# design.net
KiCad netlist of a schematic drawn in Altium Designer
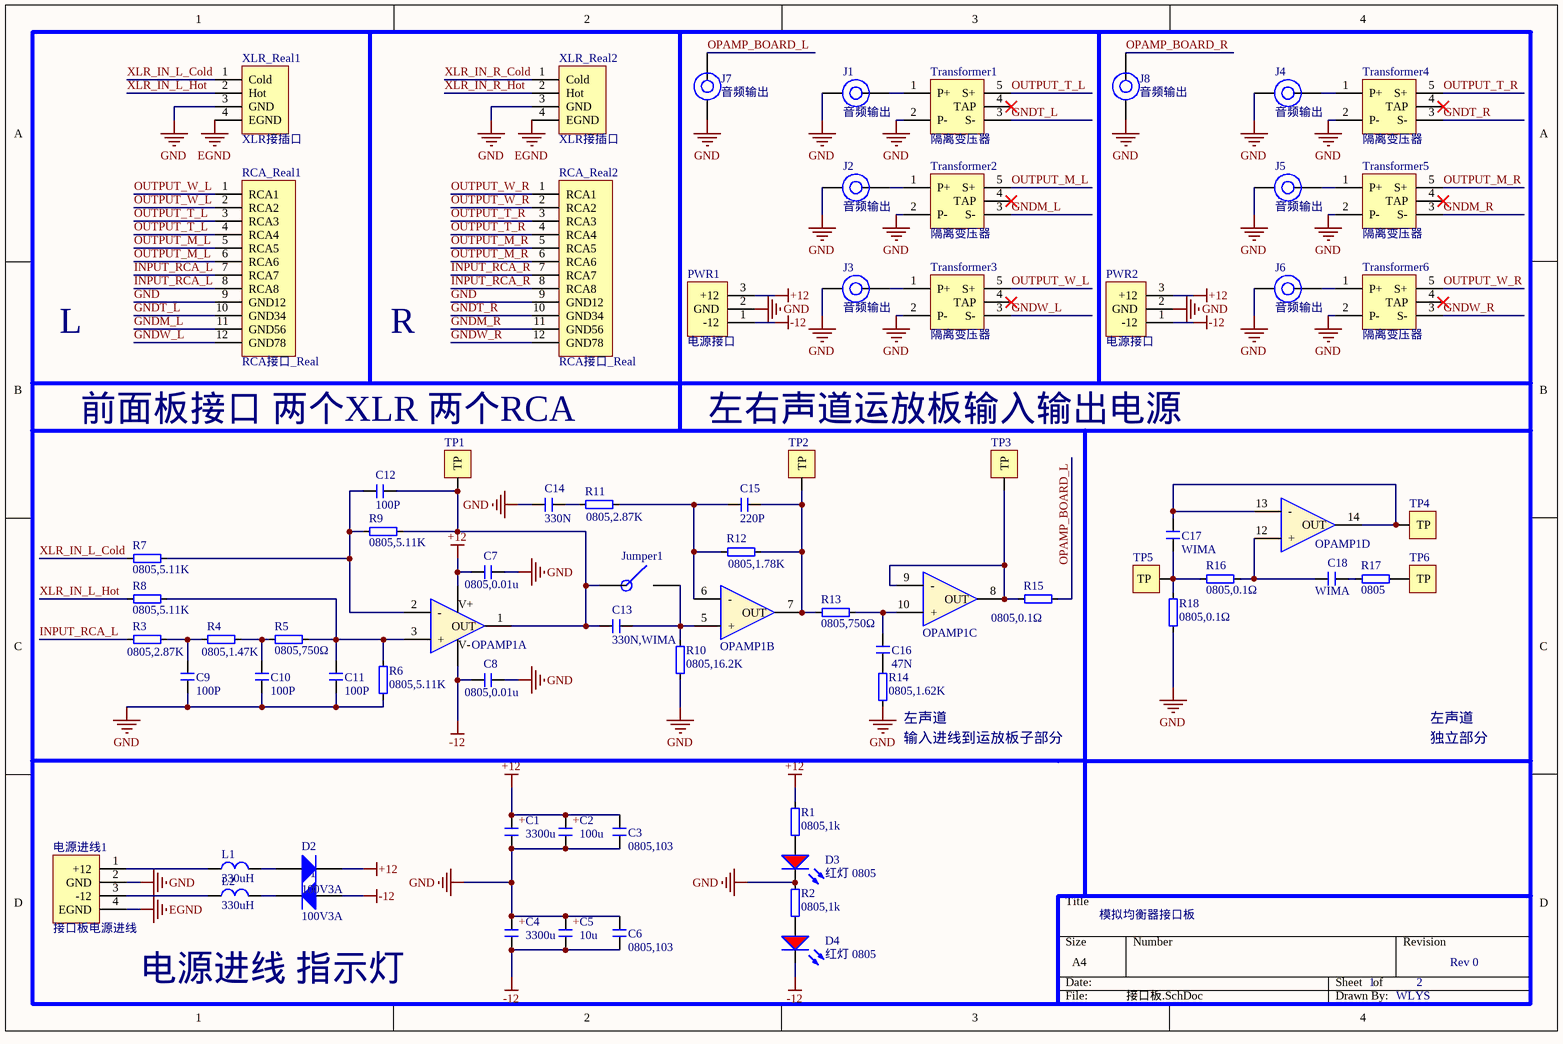
[diagram p0: 接口板.SchDoc]

(export (version "E")
  (design (tool "Eeschema 10.0.6"))
  (components
    (comp (ref "C1")
      (value "3300u")
      (footprint "CAP 7.5*16*31.5 - BK")
      (libsource (lib "模拟均衡器") (part "C直插电解"))
    )
    (comp (ref "C2") (value "100u") (footprint "CAP 2.5*6.3*11.2") (libsource (lib "模拟均衡器") (part "C直插电解")))
    (comp (ref "C3") (value "0805,103") (footprint "0805_C") (libsource (lib "模拟均衡器") (part "C0805")))
    (comp (ref "C4")
      (value "3300u")
      (footprint "CAP 7.5*16*31.5 - BK")
      (libsource (lib "模拟均衡器") (part "C直插电解"))
    )
    (comp (ref "C5") (value "10u") (footprint "CAP 2.5*6.3*11.2") (libsource (lib "模拟均衡器") (part "C直插电解")))
    (comp (ref "C6") (value "0805,103") (footprint "0805_C") (libsource (lib "模拟均衡器") (part "C0805")))
    (comp (ref "C7") (value "0805,0.01u") (footprint "0805_C") (libsource (lib "模拟均衡器") (part "C0805")))
    (comp (ref "C8") (value "0805,0.01u") (footprint "0805_C") (libsource (lib "模拟均衡器") (part "C0805")))
    (comp (ref "C9") (value "100P") (footprint "WIMA_5mm") (libsource (lib "模拟均衡器") (part "WIMA_CAP_100P")))
    (comp (ref "C10") (value "100P") (footprint "WIMA_5mm") (libsource (lib "模拟均衡器") (part "WIMA_CAP_100P")))
    (comp (ref "C11") (value "100P") (footprint "WIMA_5mm") (libsource (lib "模拟均衡器") (part "WIMA_CAP_100P")))
    (comp (ref "C12") (value "100P") (footprint "WIMA_5mm") (libsource (lib "模拟均衡器") (part "WIMA_CAP_100P")))
    (comp (ref "C13")
      (value "330N,WIMA")
      (footprint "WIMA_5mmPin*10mmL")
      (libsource (lib "模拟均衡器") (part "WIMA_CAP_330N"))
    )
    (comp (ref "C14")
      (value "330N")
      (footprint "WIMA_5mmPin*10mmL")
      (libsource (lib "模拟均衡器") (part "WIMA_CAP_330N"))
    )
    (comp (ref "C15") (value "220P") (footprint "WIMA_5mm") (libsource (lib "模拟均衡器") (part "WIMA_CAP_220P")))
    (comp (ref "C16") (value "47N") (footprint "WIMA_5mm") (libsource (lib "模拟均衡器") (part "WIMA_CAP_47N")))
    (comp (ref "C17") (value "WIMA") (footprint "WIMA_5mm") (libsource (lib "模拟均衡器") (part "WIMA_CAP_100P")))
    (comp (ref "C18") (value "WIMA") (footprint "WIMA_5mm") (libsource (lib "模拟均衡器") (part "WIMA_CAP_100P")))
    (comp (ref "D1") (value "100V3A") (footprint "DO-201AD") (libsource (lib "模拟均衡器") (part "1N5401")))
    (comp (ref "D2") (value "100V3A") (footprint "DO-201AD") (libsource (lib "模拟均衡器") (part "1N5401")))
    (comp (ref "D3")
      (value "红灯 0805")
      (footprint "0805_LED_S3")
      (description "发光二极管")
      (libsource (lib "模拟均衡器") (part "0805 红灯"))
    )
    (comp (ref "D4")
      (value "红灯 0805")
      (footprint "0805_LED_S3")
      (description "发光二极管")
      (libsource (lib "模拟均衡器") (part "0805 红灯"))
    )
    (comp (ref "J1") (value "音频输出") (footprint "XH2.54-LI-2P") (libsource (lib "模拟均衡器") (part "音频输出")))
    (comp (ref "J2") (value "音频输出") (footprint "XH2.54-LI-2P") (libsource (lib "模拟均衡器") (part "音频输出")))
    (comp (ref "J3") (value "音频输出") (footprint "XH2.54-LI-2P") (libsource (lib "模拟均衡器") (part "音频输出")))
    (comp (ref "J4") (value "音频输出") (footprint "XH2.54-LI-2P") (libsource (lib "模拟均衡器") (part "音频输出")))
    (comp (ref "J5") (value "音频输出") (footprint "XH2.54-LI-2P") (libsource (lib "模拟均衡器") (part "音频输出")))
    (comp (ref "J6") (value "音频输出") (footprint "XH2.54-LI-2P") (libsource (lib "模拟均衡器") (part "音频输出")))
    (comp (ref "J7") (value "音频输出") (footprint "XH2.54-LI-2P") (libsource (lib "模拟均衡器") (part "音频输出")))
    (comp (ref "J8") (value "音频输出") (footprint "XH2.54-LI-2P") (libsource (lib "模拟均衡器") (part "音频输出")))
    (comp (ref "Jumper1") (value "Jumper") (footprint "0805_J") (libsource (lib "模拟均衡器") (part "Jumper")))
    (comp (ref "L1") (value "330uH") (footprint "Inductor") (libsource (lib "模拟均衡器") (part "直插裸体电感330uH")))
    (comp (ref "L2") (value "330uH") (footprint "Inductor") (libsource (lib "模拟均衡器") (part "直插裸体电感330uH")))
    (comp (ref "OPAMP1")
      (value "4277UA")
      (footprint "SOIC-14_150mil")
      (libsource (lib "模拟均衡器") (part "OPA4277UA"))
    )
    (comp (ref "PWR1") (value "电源接口") (footprint "XH2.54-LI-3P") (libsource (lib "模拟均衡器") (part "电源接口")))
    (comp (ref "PWR2") (value "电源接口") (footprint "XH2.54-LI-3P") (libsource (lib "模拟均衡器") (part "电源接口")))
    (comp (ref "R1") (value "0805,1k") (footprint "0805_R") (libsource (lib "模拟均衡器") (part "R0805")))
    (comp (ref "R2") (value "0805,1k") (footprint "0805_R") (libsource (lib "模拟均衡器") (part "R0805")))
    (comp (ref "R3") (value "0805,2.87K") (footprint "0805_R") (libsource (lib "模拟均衡器") (part "R0805")))
    (comp (ref "R4") (value "0805,1.47K") (footprint "0805_R") (libsource (lib "模拟均衡器") (part "R0805")))
    (comp (ref "R5") (value "0805,750Ω") (footprint "0805_R") (libsource (lib "模拟均衡器") (part "R0805")))
    (comp (ref "R6") (value "0805,5.11K") (footprint "0805_R") (libsource (lib "模拟均衡器") (part "R0805")))
    (comp (ref "R7") (value "0805,5.11K") (footprint "0805_R") (libsource (lib "模拟均衡器") (part "R0805")))
    (comp (ref "R8") (value "0805,5.11K") (footprint "0805_R") (libsource (lib "模拟均衡器") (part "R0805")))
    (comp (ref "R9") (value "0805,5.11K") (footprint "0805_R") (libsource (lib "模拟均衡器") (part "R0805")))
    (comp (ref "R10") (value "0805,16.2K") (footprint "0805_R") (libsource (lib "模拟均衡器") (part "R0805")))
    (comp (ref "R11") (value "0805,2.87K") (footprint "0805_R") (libsource (lib "模拟均衡器") (part "R0805")))
    (comp (ref "R12") (value "0805,1.78K") (footprint "0805_R") (libsource (lib "模拟均衡器") (part "R0805")))
    (comp (ref "R13") (value "0805,750Ω") (footprint "0805_R") (libsource (lib "模拟均衡器") (part "R0805")))
    (comp (ref "R14") (value "0805,1.62K") (footprint "0805_R") (libsource (lib "模拟均衡器") (part "R0805")))
    (comp (ref "R15") (value "0805,0.1Ω") (footprint "0805_R") (libsource (lib "模拟均衡器") (part "R0805")))
    (comp (ref "R16") (value "0805,0.1Ω") (footprint "0805_R") (libsource (lib "模拟均衡器") (part "R0805")))
    (comp (ref "R17") (value "0805") (footprint "0805_R") (libsource (lib "模拟均衡器") (part "R0805")))
    (comp (ref "R18") (value "0805,0.1Ω") (footprint "0805_R") (libsource (lib "模拟均衡器") (part "R0805")))
    (comp (ref "RCA_Real1")
      (value "RCA接口_Real")
      (footprint "RCA_Real")
      (libsource (lib "模拟均衡器") (part "RCA接口_Real"))
    )
    (comp (ref "RCA_Real2")
      (value "RCA接口_Real")
      (footprint "RCA_Real")
      (libsource (lib "模拟均衡器") (part "RCA接口_Real"))
    )
    (comp (ref "TP1") (value "测试点") (footprint "TestPoint") (libsource (lib "模拟均衡器") (part "测试点")))
    (comp (ref "TP2") (value "测试点") (footprint "TestPoint") (libsource (lib "模拟均衡器") (part "测试点")))
    (comp (ref "TP3") (value "测试点") (footprint "TestPoint") (libsource (lib "模拟均衡器") (part "测试点")))
    (comp (ref "TP4") (value "测试点") (footprint "TestPoint") (libsource (lib "") (part "测试点_1")))
    (comp (ref "TP5") (value "测试点") (footprint "TestPoint") (libsource (lib "") (part "测试点_2")))
    (comp (ref "TP6") (value "测试点") (footprint "TestPoint") (libsource (lib "") (part "测试点_1")))
    (comp (ref "Transformer1")
      (value "隔离变压器")
      (footprint "Transformer")
      (libsource (lib "模拟均衡器") (part "隔离变压器"))
    )
    (comp (ref "Transformer2")
      (value "隔离变压器")
      (footprint "Transformer")
      (libsource (lib "模拟均衡器") (part "隔离变压器"))
    )
    (comp (ref "Transformer3")
      (value "隔离变压器")
      (footprint "Transformer")
      (libsource (lib "模拟均衡器") (part "隔离变压器"))
    )
    (comp (ref "Transformer4")
      (value "隔离变压器")
      (footprint "Transformer")
      (libsource (lib "模拟均衡器") (part "隔离变压器"))
    )
    (comp (ref "Transformer5")
      (value "隔离变压器")
      (footprint "Transformer")
      (libsource (lib "模拟均衡器") (part "隔离变压器"))
    )
    (comp (ref "Transformer6")
      (value "隔离变压器")
      (footprint "Transformer")
      (libsource (lib "模拟均衡器") (part "隔离变压器"))
    )
    (comp (ref "XLR_Real1")
      (value "XLR接插口")
      (footprint "XLR_Real")
      (libsource (lib "模拟均衡器") (part "XLR接口_Real"))
    )
    (comp (ref "XLR_Real2")
      (value "XLR接插口")
      (footprint "XLR_Real")
      (libsource (lib "模拟均衡器") (part "XLR接口_Real"))
    )
    (comp (ref "电源进线1")
      (value "接口板电源进线")
      (footprint "AC_Adaptor_Input")
      (libsource (lib "模拟均衡器") (part "接口板电源进线"))
    )
  )
  (nets
    (net (code "1") (name "+12") (class "Default")
      (node (ref "C1") (pin "1") (pinfunction "1_1") (pintype "passive"))
      (node (ref "C2") (pin "1") (pinfunction "1_1") (pintype "passive"))
      (node (ref "C3") (pin "1") (pinfunction "1_1") (pintype "passive"))
      (node (ref "C7") (pin "1") (pinfunction "1_1") (pintype "passive"))
      (node (ref "D2") (pin "2") (pinfunction "K_2") (pintype "passive"))
      (node (ref "OPAMP1") (pin "4") (pinfunction "V+_4") (pintype "passive"))
      (node (ref "PWR1") (pin "3") (pinfunction "+12_3") (pintype "passive"))
      (node (ref "PWR2") (pin "3") (pinfunction "+12_3") (pintype "passive"))
      (node (ref "R1") (pin "2") (pinfunction "2_2") (pintype "passive"))
    )
    (net (code "2") (name "-12") (class "Default")
      (node (ref "C4") (pin "2") (pinfunction "2_2") (pintype "passive"))
      (node (ref "C5") (pin "2") (pinfunction "2_2") (pintype "passive"))
      (node (ref "C6") (pin "2") (pinfunction "2_2") (pintype "passive"))
      (node (ref "C8") (pin "1") (pinfunction "1_1") (pintype "passive"))
      (node (ref "D1") (pin "1") (pinfunction "A_1") (pintype "passive"))
      (node (ref "D4") (pin "K") (pinfunction "K_K") (pintype "passive"))
      (node (ref "OPAMP1") (pin "11") (pinfunction "V-_11") (pintype "passive"))
      (node (ref "PWR1") (pin "1") (pinfunction "-12_1") (pintype "passive"))
      (node (ref "PWR2") (pin "1") (pinfunction "-12_1") (pintype "passive"))
    )
    (net (code "3") (name "/GNDM_L") (class "Default")
      (node (ref "RCA_Real1") (pin "11") (pinfunction "GND56_11") (pintype "passive"))
      (node (ref "Transformer2") (pin "3") (pinfunction "S-_3") (pintype "passive"))
    )
    (net (code "4") (name "/GNDM_R") (class "Default")
      (node (ref "RCA_Real2") (pin "11") (pinfunction "GND56_11") (pintype "passive"))
      (node (ref "Transformer5") (pin "3") (pinfunction "S-_3") (pintype "passive"))
    )
    (net (code "5") (name "/GNDT_L") (class "Default")
      (node (ref "RCA_Real1") (pin "10") (pinfunction "GND34_10") (pintype "passive"))
      (node (ref "Transformer1") (pin "3") (pinfunction "S-_3") (pintype "passive"))
    )
    (net (code "6") (name "/GNDT_R") (class "Default")
      (node (ref "RCA_Real2") (pin "10") (pinfunction "GND34_10") (pintype "passive"))
      (node (ref "Transformer4") (pin "3") (pinfunction "S-_3") (pintype "passive"))
    )
    (net (code "7") (name "/GNDW_L") (class "Default")
      (node (ref "RCA_Real1") (pin "12") (pinfunction "GND78_12") (pintype "passive"))
      (node (ref "Transformer3") (pin "3") (pinfunction "S-_3") (pintype "passive"))
    )
    (net (code "8") (name "/GNDW_R") (class "Default")
      (node (ref "RCA_Real2") (pin "12") (pinfunction "GND78_12") (pintype "passive"))
      (node (ref "Transformer6") (pin "3") (pinfunction "S-_3") (pintype "passive"))
    )
    (net (code "9") (name "/INPUT_RCA_L") (class "Default")
      (node (ref "R3") (pin "1") (pinfunction "1_1") (pintype "passive"))
      (node (ref "RCA_Real1") (pin "7") (pinfunction "RCA7_7") (pintype "passive"))
      (node (ref "RCA_Real1") (pin "8") (pinfunction "RCA8_8") (pintype "passive"))
    )
    (net (code "10") (name "/INPUT_RCA_R") (class "Default")
      (node (ref "RCA_Real2") (pin "7") (pinfunction "RCA7_7") (pintype "passive"))
      (node (ref "RCA_Real2") (pin "8") (pinfunction "RCA8_8") (pintype "passive"))
    )
    (net (code "11") (name "/OPAMP_BOARD_L") (class "Default")
      (node (ref "J7") (pin "1") (pinfunction "MIC_1") (pintype "passive"))
      (node (ref "R15") (pin "2") (pinfunction "2_2") (pintype "passive"))
    )
    (net (code "12") (name "/OPAMP_BOARD_R") (class "Default")
      (node (ref "J8") (pin "1") (pinfunction "MIC_1") (pintype "passive"))
    )
    (net (code "13") (name "/OUTPUT_M_L") (class "Default")
      (node (ref "RCA_Real1") (pin "5") (pinfunction "RCA5_5") (pintype "passive"))
      (node (ref "RCA_Real1") (pin "6") (pinfunction "RCA6_6") (pintype "passive"))
      (node (ref "Transformer2") (pin "5") (pinfunction "S+_5") (pintype "passive"))
    )
    (net (code "14") (name "/OUTPUT_M_R") (class "Default")
      (node (ref "RCA_Real2") (pin "5") (pinfunction "RCA5_5") (pintype "passive"))
      (node (ref "RCA_Real2") (pin "6") (pinfunction "RCA6_6") (pintype "passive"))
      (node (ref "Transformer5") (pin "5") (pinfunction "S+_5") (pintype "passive"))
    )
    (net (code "15") (name "/OUTPUT_T_L") (class "Default")
      (node (ref "RCA_Real1") (pin "3") (pinfunction "RCA3_3") (pintype "passive"))
      (node (ref "RCA_Real1") (pin "4") (pinfunction "RCA4_4") (pintype "passive"))
      (node (ref "Transformer1") (pin "5") (pinfunction "S+_5") (pintype "passive"))
    )
    (net (code "16") (name "/OUTPUT_T_R") (class "Default")
      (node (ref "RCA_Real2") (pin "3") (pinfunction "RCA3_3") (pintype "passive"))
      (node (ref "RCA_Real2") (pin "4") (pinfunction "RCA4_4") (pintype "passive"))
      (node (ref "Transformer4") (pin "5") (pinfunction "S+_5") (pintype "passive"))
    )
    (net (code "17") (name "/OUTPUT_W_L") (class "Default")
      (node (ref "RCA_Real1") (pin "1") (pinfunction "RCA1_1") (pintype "passive"))
      (node (ref "RCA_Real1") (pin "2") (pinfunction "RCA2_2") (pintype "passive"))
      (node (ref "Transformer3") (pin "5") (pinfunction "S+_5") (pintype "passive"))
    )
    (net (code "18") (name "/OUTPUT_W_R") (class "Default")
      (node (ref "RCA_Real2") (pin "1") (pinfunction "RCA1_1") (pintype "passive"))
      (node (ref "RCA_Real2") (pin "2") (pinfunction "RCA2_2") (pintype "passive"))
      (node (ref "Transformer6") (pin "5") (pinfunction "S+_5") (pintype "passive"))
    )
    (net (code "19") (name "/XLR_IN_L_Cold") (class "Default")
      (node (ref "R7") (pin "2") (pinfunction "2_2") (pintype "passive"))
      (node (ref "XLR_Real1") (pin "1") (pinfunction "Cold_1") (pintype "passive"))
    )
    (net (code "20") (name "/XLR_IN_L_Hot") (class "Default")
      (node (ref "R8") (pin "2") (pinfunction "2_2") (pintype "passive"))
      (node (ref "XLR_Real1") (pin "2") (pinfunction "Hot_2") (pintype "passive"))
    )
    (net (code "21") (name "/XLR_IN_R_Cold") (class "Default")
      (node (ref "XLR_Real2") (pin "1") (pinfunction "Cold_1") (pintype "passive"))
    )
    (net (code "22") (name "/XLR_IN_R_Hot") (class "Default")
      (node (ref "XLR_Real2") (pin "2") (pinfunction "Hot_2") (pintype "passive"))
    )
    (net (code "23") (name "EGND") (class "Default")
      (node (ref "XLR_Real1") (pin "4") (pinfunction "EGND_4") (pintype "passive"))
      (node (ref "XLR_Real2") (pin "4") (pinfunction "EGND_4") (pintype "passive"))
      (node (ref "电源进线1") (pin "4") (pinfunction "EGND_4") (pintype "passive"))
    )
    (net (code "24") (name "GND") (class "Default")
      (node (ref "C1") (pin "2") (pinfunction "2_2") (pintype "passive"))
      (node (ref "C10") (pin "2") (pinfunction "2_2") (pintype "passive"))
      (node (ref "C11") (pin "2") (pinfunction "2_2") (pintype "passive"))
      (node (ref "C14") (pin "1") (pinfunction "1_1") (pintype "passive"))
      (node (ref "C2") (pin "2") (pinfunction "2_2") (pintype "passive"))
      (node (ref "C3") (pin "2") (pinfunction "2_2") (pintype "passive"))
      (node (ref "C4") (pin "1") (pinfunction "1_1") (pintype "passive"))
      (node (ref "C5") (pin "1") (pinfunction "1_1") (pintype "passive"))
      (node (ref "C6") (pin "1") (pinfunction "1_1") (pintype "passive"))
      (node (ref "C7") (pin "2") (pinfunction "2_2") (pintype "passive"))
      (node (ref "C8") (pin "2") (pinfunction "2_2") (pintype "passive"))
      (node (ref "C9") (pin "2") (pinfunction "2_2") (pintype "passive"))
      (node (ref "D3") (pin "K") (pinfunction "K_K") (pintype "passive"))
      (node (ref "J1") (pin "2") (pinfunction "GND_2") (pintype "passive"))
      (node (ref "J2") (pin "2") (pinfunction "GND_2") (pintype "passive"))
      (node (ref "J3") (pin "2") (pinfunction "GND_2") (pintype "passive"))
      (node (ref "J4") (pin "2") (pinfunction "GND_2") (pintype "passive"))
      (node (ref "J5") (pin "2") (pinfunction "GND_2") (pintype "passive"))
      (node (ref "J6") (pin "2") (pinfunction "GND_2") (pintype "passive"))
      (node (ref "J7") (pin "2") (pinfunction "GND_2") (pintype "passive"))
      (node (ref "J8") (pin "2") (pinfunction "GND_2") (pintype "passive"))
      (node (ref "PWR1") (pin "2") (pinfunction "GND_2") (pintype "passive"))
      (node (ref "PWR2") (pin "2") (pinfunction "GND_2") (pintype "passive"))
      (node (ref "R10") (pin "1") (pinfunction "1_1") (pintype "passive"))
      (node (ref "R14") (pin "1") (pinfunction "1_1") (pintype "passive"))
      (node (ref "R18") (pin "2") (pinfunction "2_2") (pintype "passive"))
      (node (ref "R2") (pin "2") (pinfunction "2_2") (pintype "passive"))
      (node (ref "R6") (pin "1") (pinfunction "1_1") (pintype "passive"))
      (node (ref "RCA_Real1") (pin "9") (pinfunction "GND12_9") (pintype "passive"))
      (node (ref "RCA_Real2") (pin "9") (pinfunction "GND12_9") (pintype "passive"))
      (node (ref "Transformer1") (pin "2") (pinfunction "P-_2") (pintype "passive"))
      (node (ref "Transformer2") (pin "2") (pinfunction "P-_2") (pintype "passive"))
      (node (ref "Transformer3") (pin "2") (pinfunction "P-_2") (pintype "passive"))
      (node (ref "Transformer4") (pin "2") (pinfunction "P-_2") (pintype "passive"))
      (node (ref "Transformer5") (pin "2") (pinfunction "P-_2") (pintype "passive"))
      (node (ref "Transformer6") (pin "2") (pinfunction "P-_2") (pintype "passive"))
      (node (ref "XLR_Real1") (pin "3") (pinfunction "GND_3") (pintype "passive"))
      (node (ref "XLR_Real2") (pin "3") (pinfunction "GND_3") (pintype "passive"))
      (node (ref "电源进线1") (pin "2") (pinfunction "GND_2") (pintype "passive"))
    )
    (net (code "25") (name "Net-(C9-Pad1)") (class "Default")
      (node (ref "C9") (pin "1") (pinfunction "1_1") (pintype "passive"))
      (node (ref "R3") (pin "2") (pinfunction "2_2") (pintype "passive"))
      (node (ref "R4") (pin "1") (pinfunction "1_1") (pintype "passive"))
    )
    (net (code "26") (name "Net-(C10-Pad1)") (class "Default")
      (node (ref "C10") (pin "1") (pinfunction "1_1") (pintype "passive"))
      (node (ref "R4") (pin "2") (pinfunction "2_2") (pintype "passive"))
      (node (ref "R5") (pin "1") (pinfunction "1_1") (pintype "passive"))
    )
    (net (code "27") (name "Net-(C14-Pad2)") (class "Default")
      (node (ref "C14") (pin "2") (pinfunction "2_2") (pintype "passive"))
      (node (ref "R11") (pin "1") (pinfunction "1_1") (pintype "passive"))
    )
    (net (code "28") (name "Net-(C16-Pad2)") (class "Default")
      (node (ref "C16") (pin "2") (pinfunction "2_2") (pintype "passive"))
      (node (ref "R14") (pin "2") (pinfunction "2_2") (pintype "passive"))
    )
    (net (code "29") (name "Net-(C18-Pad2)") (class "Default")
      (node (ref "C18") (pin "2") (pinfunction "2_2") (pintype "passive"))
      (node (ref "R17") (pin "2") (pinfunction "2_2") (pintype "passive"))
    )
    (net (code "30") (name "Net-(D1-K)") (class "Default")
      (node (ref "D1") (pin "2") (pinfunction "K_2") (pintype "passive"))
      (node (ref "L2") (pin "2") (pinfunction "2_2") (pintype "passive"))
    )
    (net (code "31") (name "Net-(D2-A)") (class "Default")
      (node (ref "D2") (pin "1") (pinfunction "A_1") (pintype "passive"))
      (node (ref "L1") (pin "2") (pinfunction "2_2") (pintype "passive"))
    )
    (net (code "32") (name "Net-(D3-PadA)") (class "Default")
      (node (ref "D3") (pin "A") (pinfunction "A_A") (pintype "passive"))
      (node (ref "R1") (pin "1") (pinfunction "1_1") (pintype "passive"))
    )
    (net (code "33") (name "Net-(D4-PadA)") (class "Default")
      (node (ref "D4") (pin "A") (pinfunction "A_A") (pintype "passive"))
      (node (ref "R2") (pin "1") (pinfunction "1_1") (pintype "passive"))
    )
    (net (code "34") (name "Net-(J1-MIC)") (class "Default")
      (node (ref "J1") (pin "1") (pinfunction "MIC_1") (pintype "passive"))
      (node (ref "Transformer1") (pin "1") (pinfunction "P+_1") (pintype "passive"))
    )
    (net (code "35") (name "Net-(J2-MIC)") (class "Default")
      (node (ref "J2") (pin "1") (pinfunction "MIC_1") (pintype "passive"))
      (node (ref "Transformer2") (pin "1") (pinfunction "P+_1") (pintype "passive"))
    )
    (net (code "36") (name "Net-(J3-MIC)") (class "Default")
      (node (ref "J3") (pin "1") (pinfunction "MIC_1") (pintype "passive"))
      (node (ref "Transformer3") (pin "1") (pinfunction "P+_1") (pintype "passive"))
    )
    (net (code "37") (name "Net-(J4-MIC)") (class "Default")
      (node (ref "J4") (pin "1") (pinfunction "MIC_1") (pintype "passive"))
      (node (ref "Transformer4") (pin "1") (pinfunction "P+_1") (pintype "passive"))
    )
    (net (code "38") (name "Net-(J5-MIC)") (class "Default")
      (node (ref "J5") (pin "1") (pinfunction "MIC_1") (pintype "passive"))
      (node (ref "Transformer5") (pin "1") (pinfunction "P+_1") (pintype "passive"))
    )
    (net (code "39") (name "Net-(J6-MIC)") (class "Default")
      (node (ref "J6") (pin "1") (pinfunction "MIC_1") (pintype "passive"))
      (node (ref "Transformer6") (pin "1") (pinfunction "P+_1") (pintype "passive"))
    )
    (net (code "40") (name "Net-(OPAMP1A-+)") (class "Default")
      (node (ref "C11") (pin "1") (pinfunction "1_1") (pintype "passive"))
      (node (ref "OPAMP1") (pin "3") (pinfunction "+_3") (pintype "passive"))
      (node (ref "R5") (pin "2") (pinfunction "2_2") (pintype "passive"))
      (node (ref "R6") (pin "2") (pinfunction "2_2") (pintype "passive"))
      (node (ref "R8") (pin "1") (pinfunction "1_1") (pintype "passive"))
    )
    (net (code "41") (name "Net-(OPAMP1A--)") (class "Default")
      (node (ref "C12") (pin "1") (pinfunction "1_1") (pintype "passive"))
      (node (ref "OPAMP1") (pin "2") (pinfunction "-_2") (pintype "passive"))
      (node (ref "R7") (pin "1") (pinfunction "1_1") (pintype "passive"))
      (node (ref "R9") (pin "1") (pinfunction "1_1") (pintype "passive"))
    )
    (net (code "42") (name "Net-(OPAMP1A-OUT)") (class "Default")
      (node (ref "C12") (pin "2") (pinfunction "2_2") (pintype "passive"))
      (node (ref "C13") (pin "1") (pinfunction "1_1") (pintype "passive"))
      (node (ref "Jumper1") (pin "1") (pinfunction "1_1") (pintype "passive"))
      (node (ref "OPAMP1") (pin "1") (pinfunction "OUT_1") (pintype "passive"))
      (node (ref "R9") (pin "2") (pinfunction "2_2") (pintype "passive"))
      (node (ref "TP1") (pin "1") (pinfunction "TP_1") (pintype "passive"))
    )
    (net (code "43") (name "Net-(OPAMP1B-+)") (class "Default")
      (node (ref "C13") (pin "2") (pinfunction "2_2") (pintype "passive"))
      (node (ref "Jumper1") (pin "2") (pinfunction "2_2") (pintype "passive"))
      (node (ref "OPAMP1") (pin "5") (pinfunction "+_5") (pintype "passive"))
      (node (ref "R10") (pin "2") (pinfunction "2_2") (pintype "passive"))
    )
    (net (code "44") (name "Net-(OPAMP1B--)") (class "Default")
      (node (ref "C15") (pin "1") (pinfunction "1_1") (pintype "passive"))
      (node (ref "OPAMP1") (pin "6") (pinfunction "-_6") (pintype "passive"))
      (node (ref "R11") (pin "2") (pinfunction "2_2") (pintype "passive"))
      (node (ref "R12") (pin "1") (pinfunction "1_1") (pintype "passive"))
    )
    (net (code "45") (name "Net-(OPAMP1B-OUT)") (class "Default")
      (node (ref "C15") (pin "2") (pinfunction "2_2") (pintype "passive"))
      (node (ref "OPAMP1") (pin "7") (pinfunction "OUT_7") (pintype "passive"))
      (node (ref "R12") (pin "2") (pinfunction "2_2") (pintype "passive"))
      (node (ref "R13") (pin "1") (pinfunction "1_1") (pintype "passive"))
      (node (ref "TP2") (pin "1") (pinfunction "TP_1") (pintype "passive"))
    )
    (net (code "46") (name "Net-(OPAMP1C-+)") (class "Default")
      (node (ref "C16") (pin "1") (pinfunction "1_1") (pintype "passive"))
      (node (ref "OPAMP1") (pin "10") (pinfunction "+_10") (pintype "passive"))
      (node (ref "R13") (pin "2") (pinfunction "2_2") (pintype "passive"))
    )
    (net (code "47") (name "Net-(OPAMP1C--)") (class "Default")
      (node (ref "OPAMP1") (pin "8") (pinfunction "OUT_8") (pintype "passive"))
      (node (ref "OPAMP1") (pin "9") (pinfunction "-_9") (pintype "passive"))
      (node (ref "R15") (pin "1") (pinfunction "1_1") (pintype "passive"))
      (node (ref "TP3") (pin "1") (pinfunction "TP_1") (pintype "passive"))
    )
    (net (code "48") (name "Net-(OPAMP1D-+)") (class "Default")
      (node (ref "C18") (pin "1") (pinfunction "1_1") (pintype "passive"))
      (node (ref "OPAMP1") (pin "12") (pinfunction "+_12") (pintype "passive"))
      (node (ref "R16") (pin "1") (pinfunction "1_1") (pintype "passive"))
    )
    (net (code "49") (name "Net-(OPAMP1D--)") (class "Default")
      (node (ref "C17") (pin "1") (pinfunction "1_1") (pintype "passive"))
      (node (ref "OPAMP1") (pin "13") (pinfunction "-_13") (pintype "passive"))
      (node (ref "OPAMP1") (pin "14") (pinfunction "OUT_14") (pintype "passive"))
      (node (ref "TP4") (pin "1") (pinfunction "TP_1") (pintype "passive"))
    )
    (net (code "50") (name "Net-(TP5-TP)") (class "Default")
      (node (ref "C17") (pin "2") (pinfunction "2_2") (pintype "passive"))
      (node (ref "R16") (pin "2") (pinfunction "2_2") (pintype "passive"))
      (node (ref "R18") (pin "1") (pinfunction "1_1") (pintype "passive"))
      (node (ref "TP5") (pin "1") (pinfunction "TP_1") (pintype "passive"))
    )
    (net (code "51") (name "Net-(TP6-TP)") (class "Default")
      (node (ref "R17") (pin "1") (pinfunction "1_1") (pintype "passive"))
      (node (ref "TP6") (pin "1") (pinfunction "TP_1") (pintype "passive"))
    )
    (net (code "52") (name "Net-(电源进线1-+12)") (class "Default")
      (node (ref "L1") (pin "1") (pinfunction "1_1") (pintype "passive"))
      (node (ref "电源进线1") (pin "1") (pinfunction "+12_1") (pintype "passive"))
    )
    (net (code "53") (name "Net-(电源进线1--12)") (class "Default")
      (node (ref "L2") (pin "1") (pinfunction "1_1") (pintype "passive"))
      (node (ref "电源进线1") (pin "3") (pinfunction "-12_3") (pintype "passive"))
    )
    (net (code "54") (name "unconnected-(Transformer1-TAP-Pad4)") (class "Default")
      (node (ref "Transformer1") (pin "4") (pinfunction "TAP_4") (pintype "passive+no_connect"))
    )
    (net (code "55") (name "unconnected-(Transformer2-TAP-Pad4)") (class "Default")
      (node (ref "Transformer2") (pin "4") (pinfunction "TAP_4") (pintype "passive+no_connect"))
    )
    (net (code "56") (name "unconnected-(Transformer3-TAP-Pad4)") (class "Default")
      (node (ref "Transformer3") (pin "4") (pinfunction "TAP_4") (pintype "passive+no_connect"))
    )
    (net (code "57") (name "unconnected-(Transformer4-TAP-Pad4)") (class "Default")
      (node (ref "Transformer4") (pin "4") (pinfunction "TAP_4") (pintype "passive+no_connect"))
    )
    (net (code "58") (name "unconnected-(Transformer5-TAP-Pad4)") (class "Default")
      (node (ref "Transformer5") (pin "4") (pinfunction "TAP_4") (pintype "passive+no_connect"))
    )
    (net (code "59") (name "unconnected-(Transformer6-TAP-Pad4)") (class "Default")
      (node (ref "Transformer6") (pin "4") (pinfunction "TAP_4") (pintype "passive+no_connect"))
    )
  )
)
